# module_5_IR_TRANSMITTER.net
KiCad netlist of a schematic drawn in Altium Designer
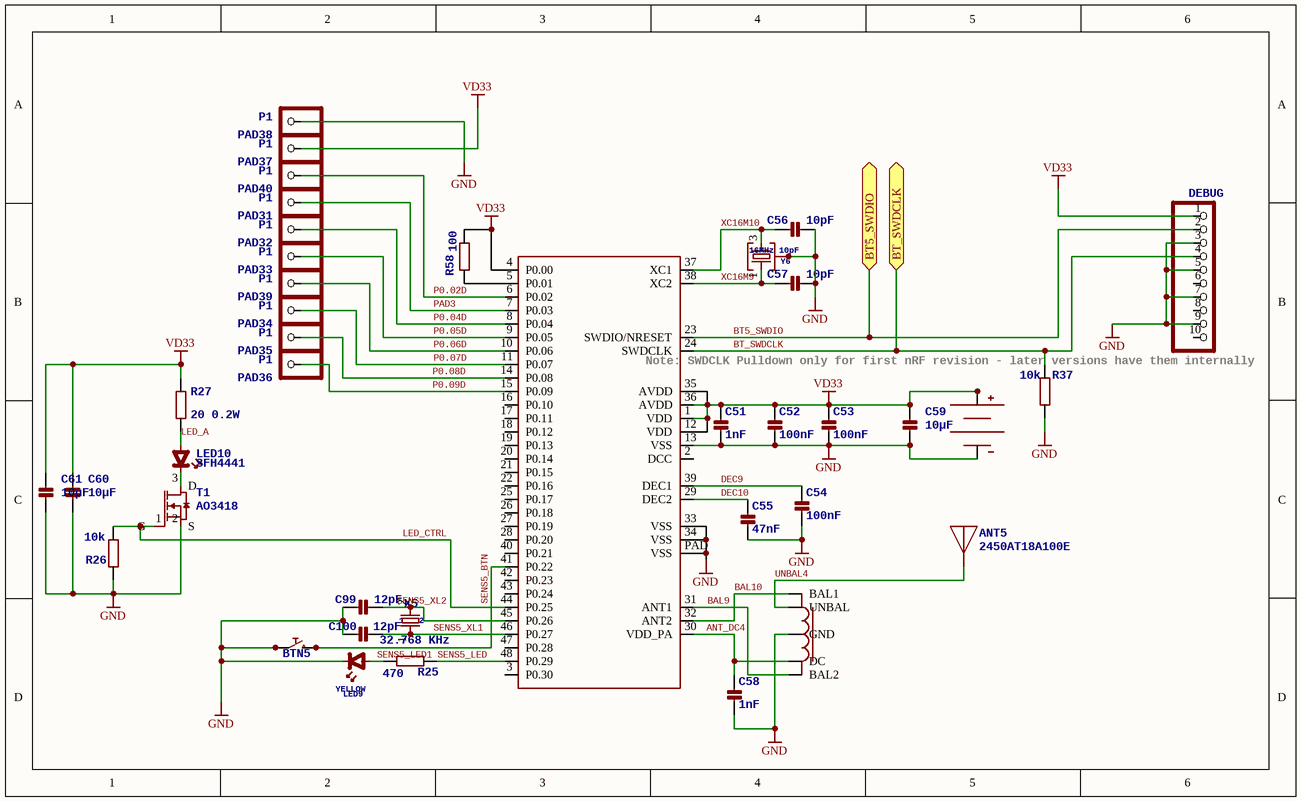
[diagram p0: module 5_IR TRANSMITTER.SchDoc]

(export (version "E")
  (design (tool "Eeschema 10.0.6"))
  (components
    (comp (ref "ANT5")
      (value "2450AT18A100E")
      (footprint "1206_MINIMELF_COMBO")
      (description "2.45 GHz Antenna")
      (libsource (lib "WunderBar_v101") (part "ANTENNA_MONOPOLE1206"))
    )
    (comp (ref "BALUN5")
      (value "2450BM14A0002T")
      (footprint "6-PIN-0603")
      (description "2.45 GHz Impedance Matched Balun-Filter")
      (libsource (lib "WunderBar_v101") (part "BALUN"))
    )
    (comp (ref "BAT5")
      (value "BATTERYBK-912")
      (footprint "BK-912")
      (description "Coin battery holder")
      (libsource (lib "WunderBar_v101") (part "BATTERYBK-912"))
    )
    (comp (ref "BT5")
      (value "NRF51822QFN48")
      (footprint "QFN48_EP")
      (description "Nordic Bluetooth 4.0 low energy modul")
      (libsource (lib "WunderBar_v101") (part "NRF51822QFN48"))
    )
    (comp (ref "BTN5")
      (value "Tact Sw 4.6x2.8")
      (footprint "CK-KMR2")
      (description "Push button")
      (libsource (lib "WunderBar_v101") (part "PUSHBUTTONKMR2XX"))
    )
    (comp (ref "C51")
      (value "1nF")
      (footprint "0402")
      (description "Ceramic Capacitor")
      (libsource (lib "WunderBar_v101") (part "CAP_CERAMIC0402"))
    )
    (comp (ref "C52")
      (value "100nF")
      (footprint "0402")
      (description "Ceramic Capacitor")
      (libsource (lib "WunderBar_v101") (part "CAP_CERAMIC0402"))
    )
    (comp (ref "C53")
      (value "100nF")
      (footprint "0402")
      (description "Ceramic Capacitor")
      (libsource (lib "WunderBar_v101") (part "CAP_CERAMIC0402"))
    )
    (comp (ref "C54")
      (value "100nF")
      (footprint "0402")
      (description "Ceramic Capacitor")
      (libsource (lib "WunderBar_v101") (part "CAP_CERAMIC0402"))
    )
    (comp (ref "C55")
      (value "47nF")
      (footprint "0402")
      (description "Ceramic Capacitor")
      (libsource (lib "WunderBar_v101") (part "CAP_CERAMIC0402"))
    )
    (comp (ref "C56")
      (value "10pF")
      (footprint "0402")
      (description "Ceramic Capacitor")
      (libsource (lib "") (part "CAP_CERAMIC0402_1"))
    )
    (comp (ref "C57")
      (value "10pF")
      (footprint "0402")
      (description "Ceramic Capacitor")
      (libsource (lib "") (part "CAP_CERAMIC0402_1"))
    )
    (comp (ref "C58")
      (value "1nF")
      (footprint "0402")
      (description "Ceramic Capacitor")
      (libsource (lib "WunderBar_v101") (part "CAP_CERAMIC0402"))
    )
    (comp (ref "C59")
      (value "10µF")
      (footprint "0603")
      (description "Ceramic Capacitor")
      (libsource (lib "WunderBar_v101") (part "CAP_CERAMIC0603"))
    )
    (comp (ref "C60")
      (value "10µF")
      (footprint "0603")
      (description "Ceramic Capacitor")
      (libsource (lib "WunderBar_v101") (part "CAP_CERAMIC0603"))
    )
    (comp (ref "C61")
      (value "10µF")
      (footprint "0603")
      (description "Ceramic Capacitor")
      (libsource (lib "WunderBar_v101") (part "CAP_CERAMIC0603"))
    )
    (comp (ref "C99")
      (value "12pF")
      (footprint "0402")
      (description "Ceramic Capacitor")
      (libsource (lib "") (part "CAP_CERAMIC0402_1"))
    )
    (comp (ref "C100")
      (value "12pF")
      (footprint "0402")
      (description "Ceramic Capacitor")
      (libsource (lib "") (part "CAP_CERAMIC0402_1"))
    )
    (comp (ref "DEBUG5")
      (value "DEBUG")
      (footprint "2X05_SMT")
      (description "cortex DEBUG connector")
      (libsource (lib "WunderBar_v101") (part "HEADER-2X5SMD-1.27MM"))
    )
    (comp (ref "LED9")
      (value "YELLOW")
      (footprint "0402_POLAR")
      (description "LED common")
      (libsource (lib "WunderBar_v101") (part "LED0402"))
    )
    (comp (ref "LED10")
      (value "SFH4441")
      (footprint "MIDLED")
      (description "LED common")
      (libsource (lib "WunderBar_v101") (part "LEDMIDLED"))
    )
    (comp (ref "PAD31")
      (value "P1")
      (footprint "PCB_MEDIUM_RECT_PAD")
      (description "<b>PIN HEADER</b>")
      (libsource (lib "WunderBar_v101") (part "HEADER-1X1SMD_MEDIUM"))
    )
    (comp (ref "PAD32")
      (value "P1")
      (footprint "PCB_MEDIUM_RECT_PAD")
      (description "<b>PIN HEADER</b>")
      (libsource (lib "WunderBar_v101") (part "HEADER-1X1SMD_MEDIUM"))
    )
    (comp (ref "PAD33")
      (value "P1")
      (footprint "PCB_MEDIUM_RECT_PAD")
      (description "<b>PIN HEADER</b>")
      (libsource (lib "WunderBar_v101") (part "HEADER-1X1SMD_MEDIUM"))
    )
    (comp (ref "PAD34")
      (value "P1")
      (footprint "PCB_MEDIUM_RECT_PAD")
      (description "<b>PIN HEADER</b>")
      (libsource (lib "WunderBar_v101") (part "HEADER-1X1SMD_MEDIUM"))
    )
    (comp (ref "PAD35")
      (value "P1")
      (footprint "PCB_MEDIUM_RECT_PAD")
      (description "<b>PIN HEADER</b>")
      (libsource (lib "WunderBar_v101") (part "HEADER-1X1SMD_MEDIUM"))
    )
    (comp (ref "PAD36")
      (value "P1")
      (footprint "PCB_MEDIUM_RECT_PAD")
      (description "<b>PIN HEADER</b>")
      (libsource (lib "WunderBar_v101") (part "HEADER-1X1SMD_MEDIUM"))
    )
    (comp (ref "PAD37")
      (value "P1")
      (footprint "PCB_MEDIUM_RECT_PAD")
      (description "<b>PIN HEADER</b>")
      (libsource (lib "WunderBar_v101") (part "HEADER-1X1SMD_MEDIUM"))
    )
    (comp (ref "PAD38")
      (value "P1")
      (footprint "PCB_MEDIUM_RECT_PAD")
      (description "<b>PIN HEADER</b>")
      (libsource (lib "WunderBar_v101") (part "HEADER-1X1SMD_MEDIUM"))
    )
    (comp (ref "PAD39")
      (value "P1")
      (footprint "PCB_MEDIUM_RECT_PAD")
      (description "<b>PIN HEADER</b>")
      (libsource (lib "WunderBar_v101") (part "HEADER-1X1SMD_MEDIUM"))
    )
    (comp (ref "PAD40")
      (value "P1")
      (footprint "PCB_MEDIUM_RECT_PAD")
      (description "<b>PIN HEADER</b>")
      (libsource (lib "WunderBar_v101") (part "HEADER-1X1SMD_MEDIUM"))
    )
    (comp (ref "R25")
      (value "470")
      (footprint "0402")
      (description "RESISTOR")
      (libsource (lib "WunderBar_v101") (part "R-EU_0402"))
    )
    (comp (ref "R26")
      (value "10k")
      (footprint "0402")
      (description "RESISTOR")
      (libsource (lib "WunderBar_v101") (part "R-EU_0402"))
    )
    (comp (ref "R27")
      (value "20 0.2W")
      (footprint "1206_MINIMELF_COMBO")
      (description "RESISTOR")
      (libsource (lib "WunderBar_v101") (part "R-EU_1206_MINIMELF_COMBO"))
    )
    (comp (ref "R37")
      (value "10k")
      (footprint "0402")
      (description "RESISTOR")
      (libsource (lib "WunderBar_v101") (part "R-EU_0402"))
    )
    (comp (ref "R58")
      (value "100")
      (footprint "0402")
      (description "RESISTOR")
      (libsource (lib "WunderBar_v101") (part "R-EU_0402"))
    )
    (comp (ref "T1")
      (value "AO3418")
      (footprint "SOT23")
      (description "N-Channel MOSFET, enhancement mode")
      (libsource (lib "WunderBar_v101") (part "NMOS_ENH"))
    )
    (comp (ref "X5")
      (value "32.768 KHz")
      (footprint "1206_MINIMELF_COMBO")
      (description "CL05C120JB5")
      (fields (field (name "1") "1") (field (name "2") "2"))
      (libsource (lib "WunderBar_v101") (part "CRYSTAL1206"))
    )
    (comp (ref "Y6")
      (value "16MHz 10pF")
      (footprint "CRYSTAL25X20")
      (description "16MHz crystal 2.5x2mm")
      (libsource (lib "WunderBar_v101") (part "CRYSTAL_WITH_GROUND25X20"))
    )
  )
  (nets
    (net (code "1") (name "/ANT_DC4") (class "Default")
      (node (ref "BALUN5") (pin "5") (pinfunction "DC_5") (pintype "power_in"))
      (node (ref "BT5") (pin "30") (pinfunction "VDD_PA_30") (pintype "passive"))
      (node (ref "C58") (pin "1") (pinfunction "1_1") (pintype "passive"))
    )
    (net (code "2") (name "/BAL9") (class "Default")
      (node (ref "BALUN5") (pin "4") (pinfunction "BAL2_4") (pintype "passive"))
      (node (ref "BT5") (pin "31") (pinfunction "ANT1_31") (pintype "passive"))
    )
    (net (code "3") (name "/BAL10") (class "Default")
      (node (ref "BALUN5") (pin "3") (pinfunction "BAL1_3") (pintype "passive"))
      (node (ref "BT5") (pin "32") (pinfunction "ANT2_32") (pintype "passive"))
    )
    (net (code "4") (name "/BT5_SWDIO") (class "Default")
      (node (ref "BT5") (pin "23") (pinfunction "SWDIO/NRESET_23") (pintype "passive"))
      (node (ref "DEBUG5") (pin "2") (pinfunction "2_2") (pintype "passive"))
    )
    (net (code "5") (name "/BT_SWDCLK") (class "Default")
      (node (ref "BT5") (pin "24") (pinfunction "SWDCLK_24") (pintype "passive"))
      (node (ref "DEBUG5") (pin "4") (pinfunction "4_4") (pintype "passive"))
      (node (ref "R37") (pin "2") (pinfunction "2_2") (pintype "passive"))
    )
    (net (code "6") (name "/DEC9") (class "Default")
      (node (ref "BT5") (pin "39") (pinfunction "DEC1_39") (pintype "passive"))
      (node (ref "C54") (pin "1") (pinfunction "1_1") (pintype "passive"))
    )
    (net (code "7") (name "/DEC10") (class "Default")
      (node (ref "BT5") (pin "29") (pinfunction "DEC2_29") (pintype "passive"))
      (node (ref "C55") (pin "1") (pinfunction "1_1") (pintype "passive"))
    )
    (net (code "8") (name "/LED_A") (class "Default")
      (node (ref "LED10") (pin "A") (pinfunction "ANODE_A") (pintype "passive"))
      (node (ref "R27") (pin "1") (pinfunction "1_1") (pintype "passive"))
    )
    (net (code "9") (name "/LED_CTRL") (class "Default")
      (node (ref "BT5") (pin "44") (pinfunction "P0.25_44") (pintype "passive"))
      (node (ref "R26") (pin "2") (pinfunction "2_2") (pintype "passive"))
      (node (ref "T1") (pin "1") (pinfunction "G_1") (pintype "passive"))
    )
    (net (code "10") (name "/P0.02D") (class "Default")
      (node (ref "BT5") (pin "6") (pinfunction "P0.02_6") (pintype "passive"))
      (node (ref "PAD40") (pin "1") (pinfunction "1_1") (pintype "passive"))
    )
    (net (code "11") (name "/P0.04D") (class "Default")
      (node (ref "BT5") (pin "8") (pinfunction "P0.04_8") (pintype "passive"))
      (node (ref "PAD32") (pin "1") (pinfunction "1_1") (pintype "passive"))
    )
    (net (code "12") (name "/P0.05D") (class "Default")
      (node (ref "BT5") (pin "9") (pinfunction "P0.05_9") (pintype "passive"))
      (node (ref "PAD33") (pin "1") (pinfunction "1_1") (pintype "passive"))
    )
    (net (code "13") (name "/P0.06D") (class "Default")
      (node (ref "BT5") (pin "10") (pinfunction "P0.06_10") (pintype "passive"))
      (node (ref "PAD39") (pin "1") (pinfunction "1_1") (pintype "passive"))
    )
    (net (code "14") (name "/P0.07D") (class "Default")
      (node (ref "BT5") (pin "11") (pinfunction "P0.07_11") (pintype "passive"))
      (node (ref "PAD34") (pin "1") (pinfunction "1_1") (pintype "passive"))
    )
    (net (code "15") (name "/P0.08D") (class "Default")
      (node (ref "BT5") (pin "14") (pinfunction "P0.08_14") (pintype "passive"))
      (node (ref "PAD35") (pin "1") (pinfunction "1_1") (pintype "passive"))
    )
    (net (code "16") (name "/P0.09D") (class "Default")
      (node (ref "BT5") (pin "15") (pinfunction "P0.09_15") (pintype "passive"))
      (node (ref "PAD36") (pin "1") (pinfunction "1_1") (pintype "passive"))
    )
    (net (code "17") (name "/PAD3") (class "Default")
      (node (ref "BT5") (pin "7") (pinfunction "P0.03_7") (pintype "passive"))
      (node (ref "PAD31") (pin "1") (pinfunction "1_1") (pintype "passive"))
    )
    (net (code "18") (name "/SENS5_BTN") (class "Default")
      (node (ref "BT5") (pin "41") (pinfunction "P0.22_41") (pintype "passive"))
      (node (ref "BTN5") (pin "P3") (pinfunction "3_P3") (pintype "passive"))
      (node (ref "BTN5") (pin "P4") (pinfunction "4_P4") (pintype "passive"))
    )
    (net (code "19") (name "/SENS5_LED") (class "Default")
      (node (ref "BT5") (pin "48") (pinfunction "P0.29_48") (pintype "passive"))
      (node (ref "R25") (pin "1") (pinfunction "1_1") (pintype "passive"))
    )
    (net (code "20") (name "/SENS5_LED1") (class "Default")
      (node (ref "LED9") (pin "A") (pinfunction "ANODE_A") (pintype "passive"))
      (node (ref "R25") (pin "2") (pinfunction "2_2") (pintype "passive"))
    )
    (net (code "21") (name "/SENS5_XL1") (class "Default")
      (node (ref "BT5") (pin "46") (pinfunction "P0.27_46") (pintype "passive"))
      (node (ref "C100") (pin "2") (pinfunction "2_2") (pintype "passive"))
      (node (ref "X5") (pin "1") (pinfunction "1_1") (pintype "passive"))
    )
    (net (code "22") (name "/SENS5_XL2") (class "Default")
      (node (ref "BT5") (pin "45") (pinfunction "P0.26_45") (pintype "passive"))
      (node (ref "C99") (pin "2") (pinfunction "2_2") (pintype "passive"))
      (node (ref "X5") (pin "2") (pinfunction "2_2") (pintype "passive"))
    )
    (net (code "23") (name "/UNBAL4") (class "Default")
      (node (ref "ANT5") (pin "1") (pinfunction "ANT_1") (pintype "passive"))
      (node (ref "BALUN5") (pin "1") (pinfunction "UNBAL_1") (pintype "passive"))
    )
    (net (code "24") (name "/XC16M9") (class "Default")
      (node (ref "BT5") (pin "38") (pinfunction "XC2_38") (pintype "passive"))
      (node (ref "C57") (pin "1") (pinfunction "1_1") (pintype "passive"))
      (node (ref "Y6") (pin "1") (pinfunction "1_1") (pintype "passive"))
    )
    (net (code "25") (name "/XC16M10") (class "Default")
      (node (ref "BT5") (pin "37") (pinfunction "XC1_37") (pintype "passive"))
      (node (ref "C56") (pin "1") (pinfunction "1_1") (pintype "passive"))
      (node (ref "Y6") (pin "3") (pinfunction "3_3") (pintype "passive"))
    )
    (net (code "26") (name "GND") (class "Default")
      (node (ref "BALUN5") (pin "2") (pinfunction "GND_2") (pintype "power_in"))
      (node (ref "BAT5") (pin "-") (pinfunction "-_-") (pintype "power_in"))
      (node (ref "BT5") (pin "13") (pinfunction "VSS_13") (pintype "passive"))
      (node (ref "BT5") (pin "33") (pinfunction "VSS_33") (pintype "passive"))
      (node (ref "BT5") (pin "34") (pinfunction "VSS_34") (pintype "passive"))
      (node (ref "BT5") (pin "PAD") (pinfunction "VSS_PAD") (pintype "passive"))
      (node (ref "BTN5") (pin "P1") (pinfunction "1_P1") (pintype "passive"))
      (node (ref "BTN5") (pin "P2") (pinfunction "2_P2") (pintype "passive"))
      (node (ref "C100") (pin "1") (pinfunction "1_1") (pintype "passive"))
      (node (ref "C51") (pin "2") (pinfunction "2_2") (pintype "passive"))
      (node (ref "C52") (pin "2") (pinfunction "2_2") (pintype "passive"))
      (node (ref "C53") (pin "2") (pinfunction "2_2") (pintype "passive"))
      (node (ref "C54") (pin "2") (pinfunction "2_2") (pintype "passive"))
      (node (ref "C55") (pin "2") (pinfunction "2_2") (pintype "passive"))
      (node (ref "C56") (pin "2") (pinfunction "2_2") (pintype "passive"))
      (node (ref "C57") (pin "2") (pinfunction "2_2") (pintype "passive"))
      (node (ref "C58") (pin "2") (pinfunction "2_2") (pintype "passive"))
      (node (ref "C59") (pin "2") (pinfunction "P2_2") (pintype "passive"))
      (node (ref "C60") (pin "2") (pinfunction "P2_2") (pintype "passive"))
      (node (ref "C61") (pin "2") (pinfunction "P2_2") (pintype "passive"))
      (node (ref "C99") (pin "1") (pinfunction "1_1") (pintype "passive"))
      (node (ref "DEBUG5") (pin "3") (pinfunction "3_3") (pintype "passive"))
      (node (ref "DEBUG5") (pin "5") (pinfunction "5_5") (pintype "passive"))
      (node (ref "DEBUG5") (pin "7") (pinfunction "7_7") (pintype "passive"))
      (node (ref "DEBUG5") (pin "9") (pinfunction "9_9") (pintype "passive"))
      (node (ref "LED9") (pin "K") (pinfunction "CATHODE_K") (pintype "passive"))
      (node (ref "PAD38") (pin "1") (pinfunction "1_1") (pintype "passive"))
      (node (ref "R26") (pin "1") (pinfunction "1_1") (pintype "passive"))
      (node (ref "R37") (pin "1") (pinfunction "1_1") (pintype "passive"))
      (node (ref "T1") (pin "2") (pinfunction "S_2") (pintype "passive"))
      (node (ref "Y6") (pin "2") (pinfunction "2_2") (pintype "power_in"))
      (node (ref "Y6") (pin "4") (pinfunction "4_4") (pintype "power_in"))
    )
    (net (code "27") (name "Net-(BT5-P0.01)") (class "Default")
      (node (ref "BT5") (pin "5") (pinfunction "P0.01_5") (pintype "passive"))
      (node (ref "R58") (pin "2") (pinfunction "2_2") (pintype "passive"))
    )
    (net (code "28") (name "Net-(LED10-CATHODE)") (class "Default")
      (node (ref "LED10") (pin "C") (pinfunction "CATHODE_C") (pintype "passive"))
      (node (ref "T1") (pin "3") (pinfunction "D_3") (pintype "passive"))
    )
    (net (code "29") (name "VD33") (class "Default")
      (node (ref "BAT5") (pin "+1") (pinfunction "+_+1") (pintype "power_in"))
      (node (ref "BAT5") (pin "+2") (pinfunction "+_+2") (pintype "power_in"))
      (node (ref "BT5") (pin "1") (pinfunction "VDD_1") (pintype "passive"))
      (node (ref "BT5") (pin "12") (pinfunction "VDD_12") (pintype "passive"))
      (node (ref "BT5") (pin "35") (pinfunction "AVDD_35") (pintype "passive"))
      (node (ref "BT5") (pin "36") (pinfunction "AVDD_36") (pintype "passive"))
      (node (ref "BT5") (pin "4") (pinfunction "P0.00_4") (pintype "passive"))
      (node (ref "C51") (pin "1") (pinfunction "1_1") (pintype "passive"))
      (node (ref "C52") (pin "1") (pinfunction "1_1") (pintype "passive"))
      (node (ref "C53") (pin "1") (pinfunction "1_1") (pintype "passive"))
      (node (ref "C59") (pin "1") (pinfunction "P1_1") (pintype "passive"))
      (node (ref "C60") (pin "1") (pinfunction "P1_1") (pintype "passive"))
      (node (ref "C61") (pin "1") (pinfunction "P1_1") (pintype "passive"))
      (node (ref "DEBUG5") (pin "1") (pinfunction "1_1") (pintype "passive"))
      (node (ref "PAD37") (pin "1") (pinfunction "1_1") (pintype "passive"))
      (node (ref "R27") (pin "2") (pinfunction "2_2") (pintype "passive"))
      (node (ref "R58") (pin "1") (pinfunction "1_1") (pintype "passive"))
    )
    (net (code "30") (name "unconnected-(BT5-DCC-Pad2)") (class "Default")
      (node (ref "BT5") (pin "2") (pinfunction "DCC_2") (pintype "passive"))
    )
    (net (code "31") (name "unconnected-(BT5-P0.10-Pad16)") (class "Default")
      (node (ref "BT5") (pin "16") (pinfunction "P0.10_16") (pintype "passive"))
    )
    (net (code "32") (name "unconnected-(BT5-P0.11-Pad17)") (class "Default")
      (node (ref "BT5") (pin "17") (pinfunction "P0.11_17") (pintype "passive"))
    )
    (net (code "33") (name "unconnected-(BT5-P0.12-Pad18)") (class "Default")
      (node (ref "BT5") (pin "18") (pinfunction "P0.12_18") (pintype "passive"))
    )
    (net (code "34") (name "unconnected-(BT5-P0.13-Pad19)") (class "Default")
      (node (ref "BT5") (pin "19") (pinfunction "P0.13_19") (pintype "passive"))
    )
    (net (code "35") (name "unconnected-(BT5-P0.14-Pad20)") (class "Default")
      (node (ref "BT5") (pin "20") (pinfunction "P0.14_20") (pintype "passive"))
    )
    (net (code "36") (name "unconnected-(BT5-P0.15-Pad21)") (class "Default")
      (node (ref "BT5") (pin "21") (pinfunction "P0.15_21") (pintype "passive"))
    )
    (net (code "37") (name "unconnected-(BT5-P0.16-Pad22)") (class "Default")
      (node (ref "BT5") (pin "22") (pinfunction "P0.16_22") (pintype "passive"))
    )
    (net (code "38") (name "unconnected-(BT5-P0.17-Pad25)") (class "Default")
      (node (ref "BT5") (pin "25") (pinfunction "P0.17_25") (pintype "passive"))
    )
    (net (code "39") (name "unconnected-(BT5-P0.18-Pad26)") (class "Default")
      (node (ref "BT5") (pin "26") (pinfunction "P0.18_26") (pintype "passive"))
    )
    (net (code "40") (name "unconnected-(BT5-P0.19-Pad27)") (class "Default")
      (node (ref "BT5") (pin "27") (pinfunction "P0.19_27") (pintype "passive"))
    )
    (net (code "41") (name "unconnected-(BT5-P0.20-Pad28)") (class "Default")
      (node (ref "BT5") (pin "28") (pinfunction "P0.20_28") (pintype "passive"))
    )
    (net (code "42") (name "unconnected-(BT5-P0.21-Pad40)") (class "Default")
      (node (ref "BT5") (pin "40") (pinfunction "P0.21_40") (pintype "passive"))
    )
    (net (code "43") (name "unconnected-(BT5-P0.23-Pad42)") (class "Default")
      (node (ref "BT5") (pin "42") (pinfunction "P0.23_42") (pintype "passive"))
    )
    (net (code "44") (name "unconnected-(BT5-P0.24-Pad43)") (class "Default")
      (node (ref "BT5") (pin "43") (pinfunction "P0.24_43") (pintype "passive"))
    )
    (net (code "45") (name "unconnected-(BT5-P0.28-Pad47)") (class "Default")
      (node (ref "BT5") (pin "47") (pinfunction "P0.28_47") (pintype "passive"))
    )
    (net (code "46") (name "unconnected-(BT5-P0.30-Pad3)") (class "Default")
      (node (ref "BT5") (pin "3") (pinfunction "P0.30_3") (pintype "passive"))
    )
    (net (code "47") (name "unconnected-(DEBUG5-Pad6)") (class "Default")
      (node (ref "DEBUG5") (pin "6") (pinfunction "6_6") (pintype "passive"))
    )
    (net (code "48") (name "unconnected-(DEBUG5-Pad8)") (class "Default")
      (node (ref "DEBUG5") (pin "8") (pinfunction "8_8") (pintype "passive"))
    )
    (net (code "49") (name "unconnected-(DEBUG5-Pad10)") (class "Default")
      (node (ref "DEBUG5") (pin "10") (pinfunction "10_10") (pintype "passive"))
    )
  )
)
